# SWD_resistor_hack.net
KiCad netlist of a schematic drawn in Altium Designer
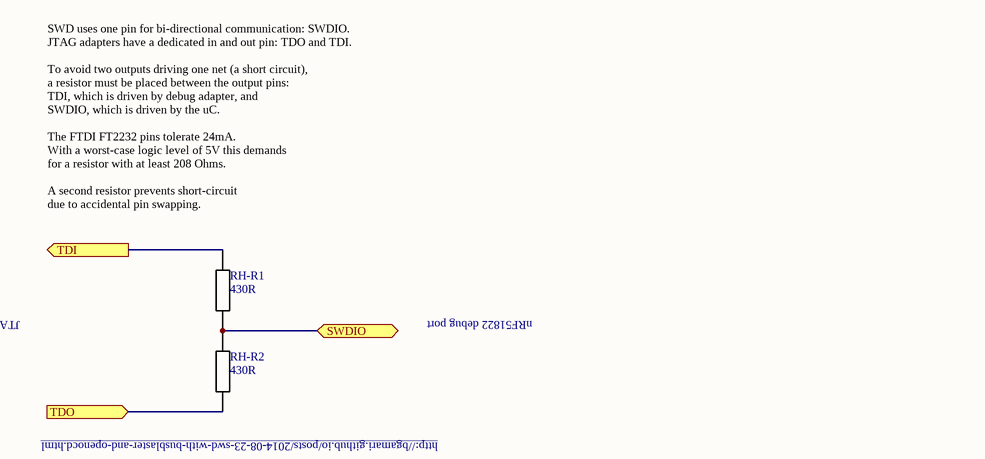
[diagram p0: SWD resistor hack.SchDoc]

(export (version "E")
  (design (tool "Eeschema 10.0.6"))
  (components
    (comp (ref "RH-R1")
      (value "430R")
      (footprint "R 0805 / 2012")
      (libsource (lib "Core51822-related") (part "Resistor"))
    )
    (comp (ref "RH-R2")
      (value "430R")
      (footprint "R 0805 / 2012")
      (libsource (lib "Core51822-related") (part "Resistor"))
    )
  )
  (nets
    (net (code "1") (name "/SWDIO") (class "Default")
      (node (ref "RH-R1") (pin "1") (pinfunction "1_1") (pintype "passive"))
      (node (ref "RH-R2") (pin "2") (pinfunction "2_2") (pintype "passive"))
    )
    (net (code "2") (name "/TDI") (class "Default")
      (node (ref "RH-R1") (pin "2") (pinfunction "2_2") (pintype "passive"))
    )
    (net (code "3") (name "/TDO") (class "Default")
      (node (ref "RH-R2") (pin "1") (pinfunction "1_1") (pintype "passive"))
    )
  )
)
